# CAP-HOST.net
KiCad netlist of a schematic drawn in EAGLE
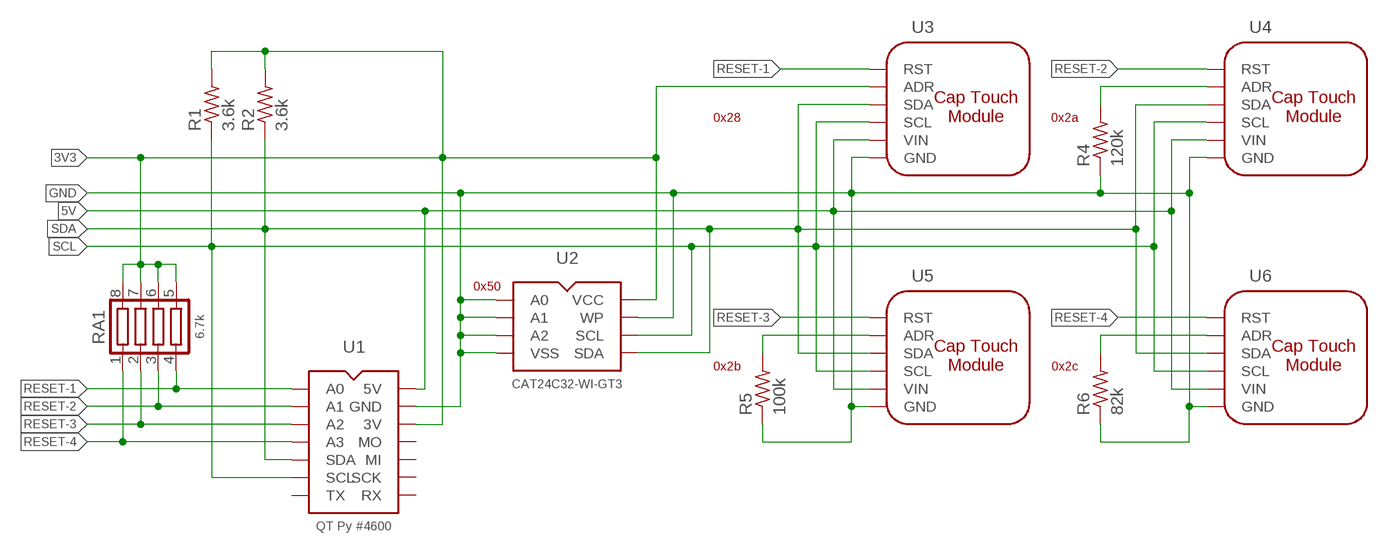
[diagram p0: schematic, sheet 1]

(export (version "E")
  (design (tool "Eeschema 10.0.6"))
  (components
    (comp (ref "R1")
      (value "3.6k")
      (footprint "eagle-import:R1206")
      (libsource (lib "eagle-import") (part "R-US_R1206"))
    )
    (comp (ref "R2")
      (value "3.6k")
      (footprint "eagle-import:R1206")
      (libsource (lib "eagle-import") (part "R-US_R1206"))
    )
    (comp (ref "R4")
      (value "120k")
      (footprint "eagle-import:R1206")
      (libsource (lib "eagle-import") (part "R-US_R1206"))
    )
    (comp (ref "R5")
      (value "100k")
      (footprint "eagle-import:R1206")
      (libsource (lib "eagle-import") (part "R-US_R1206"))
    )
    (comp (ref "R6")
      (value "82k")
      (footprint "eagle-import:R1206")
      (libsource (lib "eagle-import") (part "R-US_R1206"))
    )
    (comp (ref "RA1")
      (value "6.7k")
      (footprint "eagle-import:RES-NET-1206")
      (libsource (lib "eagle-import") (part "RES-ARRAY-1206"))
    )
    (comp (ref "U1")
      (value "QT Py #4600")
      (footprint "eagle-import:QT_PY-CASTL")
      (libsource (lib "eagle-import") (part "QT_PY-CASTL"))
    )
    (comp (ref "U2")
      (value "CAT24C32-WI-GT3")
      (footprint "eagle-import:SOIC-8-ON")
      (libsource (lib "eagle-import") (part "EEPROM-I2C-CAT24C32-WI-GT3"))
    )
    (comp (ref "U3")
      (value "CAP-SENSOR-INTF")
      (footprint "eagle-import:CAP-TOUCH-MODULE-2")
      (libsource (lib "eagle-import") (part "CAP-SENSOR-INTF"))
    )
    (comp (ref "U4")
      (value "CAP-SENSOR-INTF")
      (footprint "eagle-import:CAP-TOUCH-MODULE-2")
      (libsource (lib "eagle-import") (part "CAP-SENSOR-INTF"))
    )
    (comp (ref "U5")
      (value "CAP-SENSOR-INTF")
      (footprint "eagle-import:CAP-TOUCH-MODULE-2")
      (libsource (lib "eagle-import") (part "CAP-SENSOR-INTF"))
    )
    (comp (ref "U6")
      (value "CAP-SENSOR-INTF")
      (footprint "eagle-import:CAP-TOUCH-MODULE-2")
      (libsource (lib "eagle-import") (part "CAP-SENSOR-INTF"))
    )
  )
  (nets
    (net (code "1") (name "3V3") (class "Default")
      (node (ref "R1") (pin "2") (pinfunction "2_2") (pintype "passive"))
      (node (ref "R2") (pin "2") (pinfunction "2_2") (pintype "passive"))
      (node (ref "RA1") (pin "5") (pinfunction "5_5") (pintype "passive"))
      (node (ref "RA1") (pin "6") (pinfunction "6_6") (pintype "passive"))
      (node (ref "RA1") (pin "7") (pinfunction "7_7") (pintype "passive"))
      (node (ref "RA1") (pin "8") (pinfunction "8_8") (pintype "passive"))
      (node (ref "U1") (pin "3V3") (pinfunction "3V_3V3") (pintype "power_in"))
      (node (ref "U2") (pin "P$8") (pinfunction "VCC_P$8") (pintype "bidirectional"))
      (node (ref "U3") (pin "ADR") (pinfunction "ADR_ADR") (pintype "bidirectional"))
    )
    (net (code "2") (name "5V") (class "Default")
      (node (ref "U1") (pin "5V") (pinfunction "5V_5V") (pintype "power_in"))
      (node (ref "U3") (pin "VIN") (pinfunction "VIN_VIN") (pintype "bidirectional"))
      (node (ref "U4") (pin "VIN") (pinfunction "VIN_VIN") (pintype "bidirectional"))
      (node (ref "U5") (pin "VIN") (pinfunction "VIN_VIN") (pintype "bidirectional"))
      (node (ref "U6") (pin "VIN") (pinfunction "VIN_VIN") (pintype "bidirectional"))
    )
    (net (code "3") (name "GND") (class "Default")
      (node (ref "R4") (pin "1") (pinfunction "1_1") (pintype "passive"))
      (node (ref "R5") (pin "1") (pinfunction "1_1") (pintype "passive"))
      (node (ref "R6") (pin "1") (pinfunction "1_1") (pintype "passive"))
      (node (ref "U1") (pin "GND") (pinfunction "GND_GND") (pintype "power_in"))
      (node (ref "U2") (pin "P$1") (pinfunction "A0_P$1") (pintype "bidirectional"))
      (node (ref "U2") (pin "P$2") (pinfunction "A1_P$2") (pintype "bidirectional"))
      (node (ref "U2") (pin "P$3") (pinfunction "A2_P$3") (pintype "bidirectional"))
      (node (ref "U2") (pin "P$4") (pinfunction "VSS_P$4") (pintype "bidirectional"))
      (node (ref "U2") (pin "P$7") (pinfunction "WP_P$7") (pintype "bidirectional"))
      (node (ref "U3") (pin "GND") (pinfunction "GND_GND") (pintype "bidirectional"))
      (node (ref "U4") (pin "GND") (pinfunction "GND_GND") (pintype "bidirectional"))
      (node (ref "U5") (pin "GND") (pinfunction "GND_GND") (pintype "bidirectional"))
      (node (ref "U6") (pin "GND") (pinfunction "GND_GND") (pintype "bidirectional"))
    )
    (net (code "4") (name "Net-(R4-Pad2)") (class "Default")
      (node (ref "R4") (pin "2") (pinfunction "2_2") (pintype "passive"))
      (node (ref "U4") (pin "ADR") (pinfunction "ADR_ADR") (pintype "bidirectional"))
    )
    (net (code "5") (name "Net-(R5-Pad2)") (class "Default")
      (node (ref "R5") (pin "2") (pinfunction "2_2") (pintype "passive"))
      (node (ref "U5") (pin "ADR") (pinfunction "ADR_ADR") (pintype "bidirectional"))
    )
    (net (code "6") (name "Net-(R6-Pad2)") (class "Default")
      (node (ref "R6") (pin "2") (pinfunction "2_2") (pintype "passive"))
      (node (ref "U6") (pin "ADR") (pinfunction "ADR_ADR") (pintype "bidirectional"))
    )
    (net (code "7") (name "RESET-1") (class "Default")
      (node (ref "RA1") (pin "4") (pinfunction "4_4") (pintype "passive"))
      (node (ref "U1") (pin "A0") (pinfunction "A0_A0") (pintype "bidirectional"))
      (node (ref "U3") (pin "RST") (pinfunction "RST_RST") (pintype "bidirectional"))
    )
    (net (code "8") (name "RESET-2") (class "Default")
      (node (ref "RA1") (pin "3") (pinfunction "3_3") (pintype "passive"))
      (node (ref "U1") (pin "A1") (pinfunction "A1_A1") (pintype "bidirectional"))
      (node (ref "U4") (pin "RST") (pinfunction "RST_RST") (pintype "bidirectional"))
    )
    (net (code "9") (name "RESET-3") (class "Default")
      (node (ref "RA1") (pin "2") (pinfunction "2_2") (pintype "passive"))
      (node (ref "U1") (pin "A2") (pinfunction "A2_A2") (pintype "bidirectional"))
      (node (ref "U5") (pin "RST") (pinfunction "RST_RST") (pintype "bidirectional"))
    )
    (net (code "10") (name "RESET-4") (class "Default")
      (node (ref "RA1") (pin "1") (pinfunction "1_1") (pintype "passive"))
      (node (ref "U1") (pin "A3") (pinfunction "A3_A3") (pintype "bidirectional"))
      (node (ref "U6") (pin "RST") (pinfunction "RST_RST") (pintype "bidirectional"))
    )
    (net (code "11") (name "SCL") (class "Default")
      (node (ref "R1") (pin "1") (pinfunction "1_1") (pintype "passive"))
      (node (ref "U1") (pin "SCL") (pinfunction "SCL_SCL") (pintype "bidirectional"))
      (node (ref "U2") (pin "P$6") (pinfunction "SCL_P$6") (pintype "bidirectional"))
      (node (ref "U3") (pin "SCL") (pinfunction "SCL_SCL") (pintype "bidirectional"))
      (node (ref "U4") (pin "SCL") (pinfunction "SCL_SCL") (pintype "bidirectional"))
      (node (ref "U5") (pin "SCL") (pinfunction "SCL_SCL") (pintype "bidirectional"))
      (node (ref "U6") (pin "SCL") (pinfunction "SCL_SCL") (pintype "bidirectional"))
    )
    (net (code "12") (name "SDA") (class "Default")
      (node (ref "R2") (pin "1") (pinfunction "1_1") (pintype "passive"))
      (node (ref "U1") (pin "SDA") (pinfunction "SDA_SDA") (pintype "bidirectional"))
      (node (ref "U2") (pin "P$5") (pinfunction "SDA_P$5") (pintype "bidirectional"))
      (node (ref "U3") (pin "SDA") (pinfunction "SDA_SDA") (pintype "bidirectional"))
      (node (ref "U4") (pin "SDA") (pinfunction "SDA_SDA") (pintype "bidirectional"))
      (node (ref "U5") (pin "SDA") (pinfunction "SDA_SDA") (pintype "bidirectional"))
      (node (ref "U6") (pin "SDA") (pinfunction "SDA_SDA") (pintype "bidirectional"))
    )
    (net (code "13") (name "unconnected-(U1-MI-PadMISO)") (class "Default")
      (node (ref "U1") (pin "MISO") (pinfunction "MI_MISO") (pintype "bidirectional"))
    )
    (net (code "14") (name "unconnected-(U1-MO-PadMOSI)") (class "Default")
      (node (ref "U1") (pin "MOSI") (pinfunction "MO_MOSI") (pintype "bidirectional"))
    )
    (net (code "15") (name "unconnected-(U1-PadRX)") (class "Default")
      (node (ref "U1") (pin "RX") (pinfunction "RX_RX") (pintype "bidirectional"))
    )
    (net (code "16") (name "unconnected-(U1-PadTX)") (class "Default")
      (node (ref "U1") (pin "TX") (pinfunction "TX_TX") (pintype "bidirectional"))
    )
    (net (code "17") (name "unconnected-(U1-SCK-PadSCLK)") (class "Default")
      (node (ref "U1") (pin "SCLK") (pinfunction "SCK_SCLK") (pintype "bidirectional"))
    )
  )
)
